# DaughterBoard.net
KiCad netlist of a schematic drawn in Altium Designer
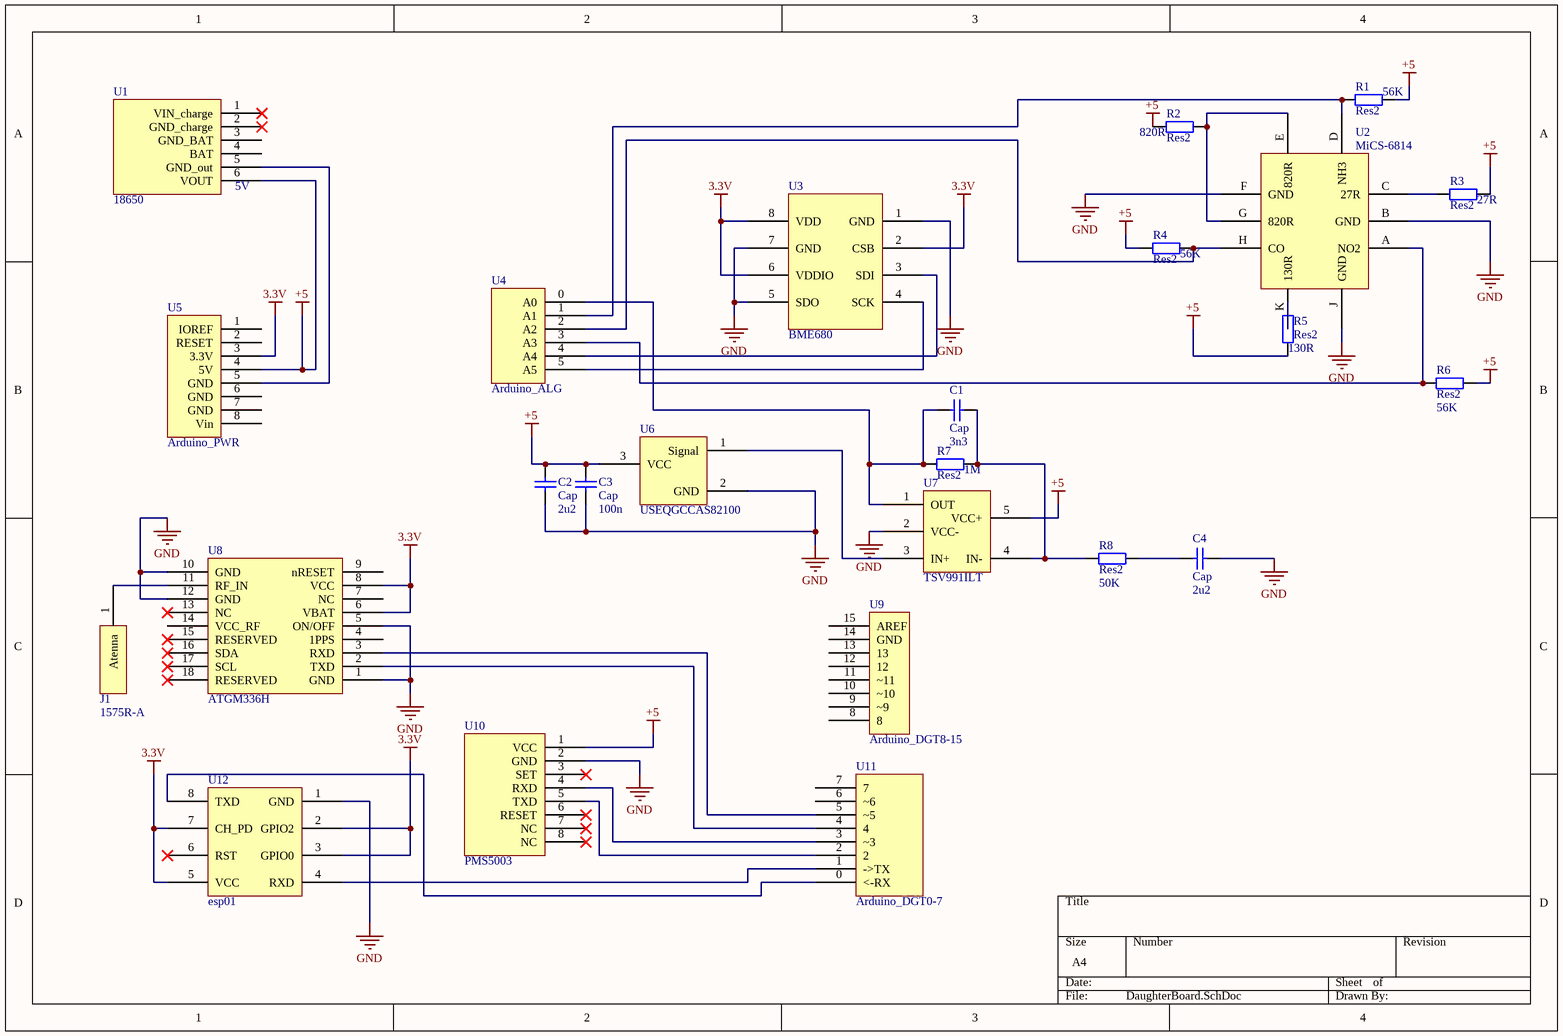
[diagram p0: DaughterBoard.SchDoc]

(export (version "E")
  (design (tool "Eeschema 10.0.6"))
  (components
    (comp (ref "C1")
      (value "Cap")
      (footprint "RAD-0.3")
      (description "Capacitor")
      (fields (field (name "ALTIUM_VALUE") "3n3") (field (name "PUBLISHER") "Altium Limited"))
      (libsource (lib "Miscellaneous Devices") (part "Cap"))
    )
    (comp (ref "C2")
      (value "Cap")
      (footprint "RAD-0.3")
      (description "Capacitor")
      (fields (field (name "ALTIUM_VALUE") "2u2") (field (name "PUBLISHER") "Altium Limited"))
      (libsource (lib "Miscellaneous Devices") (part "Cap"))
    )
    (comp (ref "C3")
      (value "Cap")
      (footprint "RAD-0.3")
      (description "Capacitor")
      (fields (field (name "ALTIUM_VALUE") "100n") (field (name "PUBLISHER") "Altium Limited"))
      (libsource (lib "Miscellaneous Devices") (part "Cap"))
    )
    (comp (ref "C4")
      (value "Cap")
      (footprint "RAD-0.3")
      (description "Capacitor")
      (fields (field (name "ALTIUM_VALUE") "2u2") (field (name "PUBLISHER") "Altium Limited"))
      (libsource (lib "Miscellaneous Devices") (part "Cap"))
    )
    (comp (ref "J1") (value "1575R-A") (libsource (lib "SDLib") (part "1575R-A")))
    (comp (ref "R1")
      (value "Res2")
      (footprint "AXIAL-0.4")
      (description "Resistor")
      (fields (field (name "ALTIUM_VALUE") "56K") (field (name "PUBLISHER") "Altium Limited"))
      (libsource (lib "") (part "Res2_2"))
    )
    (comp (ref "R2")
      (value "Res2")
      (footprint "AXIAL-0.4")
      (description "Resistor")
      (fields (field (name "ALTIUM_VALUE") "820R") (field (name "PUBLISHER") "Altium Limited"))
      (libsource (lib "Miscellaneous Devices") (part "Res2"))
    )
    (comp (ref "R3")
      (value "Res2")
      (footprint "AXIAL-0.4")
      (description "Resistor")
      (fields (field (name "ALTIUM_VALUE") "27R") (field (name "PUBLISHER") "Altium Limited"))
      (libsource (lib "Miscellaneous Devices") (part "Res2"))
    )
    (comp (ref "R4")
      (value "Res2")
      (footprint "AXIAL-0.4")
      (description "Resistor")
      (fields (field (name "ALTIUM_VALUE") "56K") (field (name "PUBLISHER") "Altium Limited"))
      (libsource (lib "Miscellaneous Devices") (part "Res2"))
    )
    (comp (ref "R5")
      (value "Res2")
      (footprint "AXIAL-0.4")
      (description "Resistor")
      (fields (field (name "ALTIUM_VALUE") "130R") (field (name "PUBLISHER") "Altium Limited"))
      (libsource (lib "") (part "Res2_1"))
    )
    (comp (ref "R6")
      (value "Res2")
      (footprint "AXIAL-0.4")
      (description "Resistor")
      (fields (field (name "ALTIUM_VALUE") "56K") (field (name "PUBLISHER") "Altium Limited"))
      (libsource (lib "") (part "Res2_2"))
    )
    (comp (ref "R7")
      (value "Res2")
      (footprint "AXIAL-0.4")
      (description "Resistor")
      (fields (field (name "ALTIUM_VALUE") "1M") (field (name "PUBLISHER") "Altium Limited"))
      (libsource (lib "Miscellaneous Devices") (part "Res2"))
    )
    (comp (ref "R8")
      (value "Res2")
      (footprint "AXIAL-0.4")
      (description "Resistor")
      (fields (field (name "ALTIUM_VALUE") "50K") (field (name "PUBLISHER") "Altium Limited"))
      (libsource (lib "") (part "Res2_2"))
    )
    (comp (ref "U1") (value "18650") (libsource (lib "SDLib") (part "18650")))
    (comp (ref "U2") (value "MiCS-6814") (libsource (lib "SDLib") (part "MiCS-6814")))
    (comp (ref "U3") (value "BME680") (libsource (lib "SDLib") (part "BME680")))
    (comp (ref "U4") (value "Arduino_ALG") (libsource (lib "SDLib") (part "Arduino_ALG")))
    (comp (ref "U5") (value "Arduino_PWR") (libsource (lib "SDLib") (part "Arduino_PWR")))
    (comp (ref "U6") (value "USEQGCCAS82100") (libsource (lib "SDLib") (part "USEQGCCAS82100")))
    (comp (ref "U7") (value "TSV991ILT") (libsource (lib "SDLib") (part "TSV991ILT")))
    (comp (ref "U8") (value "ATGM336H") (libsource (lib "SDLib") (part "ATGM336H")))
    (comp (ref "U9") (value "Arduino_DGT8-15") (libsource (lib "SDLib") (part "Arduino_DGT8-15")))
    (comp (ref "U10") (value "PMS5003") (libsource (lib "SDLib") (part "PMS5003")))
    (comp (ref "U11") (value "Arduino_DGT0-7") (libsource (lib "SDLib") (part "Arduino_DGT0-7")))
    (comp (ref "U12") (value "esp01") (libsource (lib "SDLib") (part "esp01")))
  )
  (nets
    (net (code "1") (name "+5") (class "Default")
      (node (ref "C2") (pin "2") (pinfunction "2_2") (pintype "passive"))
      (node (ref "C3") (pin "2") (pinfunction "2_2") (pintype "passive"))
      (node (ref "R1") (pin "1") (pinfunction "1_1") (pintype "passive"))
      (node (ref "R2") (pin "1") (pinfunction "1_1") (pintype "passive"))
      (node (ref "R3") (pin "2") (pinfunction "2_2") (pintype "passive"))
      (node (ref "R4") (pin "1") (pinfunction "1_1") (pintype "passive"))
      (node (ref "R5") (pin "1") (pinfunction "1_1") (pintype "passive"))
      (node (ref "R6") (pin "1") (pinfunction "1_1") (pintype "passive"))
      (node (ref "U1") (pin "6") (pinfunction "VOUT_6") (pintype "passive"))
      (node (ref "U10") (pin "1") (pinfunction "VCC_1") (pintype "passive"))
      (node (ref "U5") (pin "4") (pinfunction "5V_4") (pintype "passive"))
      (node (ref "U6") (pin "3") (pinfunction "VCC_3") (pintype "passive"))
      (node (ref "U7") (pin "5") (pinfunction "VCC+_5") (pintype "passive"))
    )
    (net (code "2") (name "3.3V") (class "Default")
      (node (ref "U12") (pin "2") (pinfunction "GPIO2_2") (pintype "passive"))
      (node (ref "U12") (pin "3") (pinfunction "GPIO0_3") (pintype "passive"))
      (node (ref "U12") (pin "5") (pinfunction "VCC_5") (pintype "passive"))
      (node (ref "U12") (pin "7") (pinfunction "CH_PD_7") (pintype "passive"))
      (node (ref "U3") (pin "2") (pinfunction "CSB_2") (pintype "passive"))
      (node (ref "U3") (pin "6") (pinfunction "VDDIO_6") (pintype "passive"))
      (node (ref "U3") (pin "8") (pinfunction "VDD_8") (pintype "passive"))
      (node (ref "U5") (pin "3") (pinfunction "3.3V_3") (pintype "power_in"))
      (node (ref "U8") (pin "6") (pinfunction "VBAT_6") (pintype "passive"))
      (node (ref "U8") (pin "8") (pinfunction "VCC_8") (pintype "passive"))
    )
    (net (code "3") (name "GND") (class "Default")
      (node (ref "C2") (pin "1") (pinfunction "1_1") (pintype "passive"))
      (node (ref "C3") (pin "1") (pinfunction "1_1") (pintype "passive"))
      (node (ref "C4") (pin "2") (pinfunction "2_2") (pintype "passive"))
      (node (ref "U10") (pin "2") (pinfunction "GND_2") (pintype "passive"))
      (node (ref "U12") (pin "1") (pinfunction "GND_1") (pintype "passive"))
      (node (ref "U2") (pin "B") (pinfunction "GND_B") (pintype "passive"))
      (node (ref "U2") (pin "F") (pinfunction "GND_F") (pintype "passive"))
      (node (ref "U2") (pin "J") (pinfunction "GND_J") (pintype "passive"))
      (node (ref "U3") (pin "1") (pinfunction "GND_1") (pintype "passive"))
      (node (ref "U3") (pin "5") (pinfunction "SDO_5") (pintype "passive"))
      (node (ref "U3") (pin "7") (pinfunction "GND_7") (pintype "passive"))
      (node (ref "U6") (pin "2") (pinfunction "GND_2") (pintype "passive"))
      (node (ref "U7") (pin "2") (pinfunction "VCC-_2") (pintype "passive"))
      (node (ref "U8") (pin "1") (pinfunction "GND_1") (pintype "passive"))
      (node (ref "U8") (pin "10") (pinfunction "GND_10") (pintype "passive"))
      (node (ref "U8") (pin "12") (pinfunction "GND_12") (pintype "passive"))
      (node (ref "U8") (pin "5") (pinfunction "ON/OFF_5") (pintype "passive"))
    )
    (net (code "4") (name "Net-(C4-Pad1)") (class "Default")
      (node (ref "C4") (pin "1") (pinfunction "1_1") (pintype "passive"))
      (node (ref "R8") (pin "1") (pinfunction "1_1") (pintype "passive"))
    )
    (net (code "5") (name "Net-(J1-Atenna)") (class "Default")
      (node (ref "J1") (pin "1") (pinfunction "Atenna_1") (pintype "passive"))
      (node (ref "U8") (pin "11") (pinfunction "RF_IN_11") (pintype "passive"))
    )
    (net (code "6") (name "Net-(R2-Pad2)") (class "Default")
      (node (ref "R2") (pin "2") (pinfunction "2_2") (pintype "passive"))
      (node (ref "U2") (pin "E") (pinfunction "820R_E") (pintype "passive"))
      (node (ref "U2") (pin "G") (pinfunction "820R_G") (pintype "passive"))
    )
    (net (code "7") (name "Net-(U1-GND_out)") (class "Default")
      (node (ref "U1") (pin "5") (pinfunction "GND_out_5") (pintype "passive"))
      (node (ref "U5") (pin "5") (pinfunction "GND_5") (pintype "power_in"))
    )
    (net (code "8") (name "Net-(U2-27R)") (class "Default")
      (node (ref "R3") (pin "1") (pinfunction "1_1") (pintype "passive"))
      (node (ref "U2") (pin "C") (pinfunction "27R_C") (pintype "passive"))
    )
    (net (code "9") (name "Net-(U2-130R)") (class "Default")
      (node (ref "R5") (pin "2") (pinfunction "2_2") (pintype "passive"))
      (node (ref "U2") (pin "K") (pinfunction "130R_K") (pintype "passive"))
    )
    (net (code "10") (name "Net-(U2-CO)") (class "Default")
      (node (ref "R4") (pin "2") (pinfunction "2_2") (pintype "passive"))
      (node (ref "U2") (pin "H") (pinfunction "CO_H") (pintype "passive"))
      (node (ref "U4") (pin "2") (pinfunction "A2_2") (pintype "passive"))
    )
    (net (code "11") (name "Net-(U2-NH3)") (class "Default")
      (node (ref "R1") (pin "2") (pinfunction "2_2") (pintype "passive"))
      (node (ref "U2") (pin "D") (pinfunction "NH3_D") (pintype "passive"))
      (node (ref "U4") (pin "1") (pinfunction "A1_1") (pintype "passive"))
    )
    (net (code "12") (name "Net-(U2-NO2)") (class "Default")
      (node (ref "R6") (pin "2") (pinfunction "2_2") (pintype "passive"))
      (node (ref "U2") (pin "A") (pinfunction "NO2_A") (pintype "passive"))
      (node (ref "U4") (pin "3") (pinfunction "A3_3") (pintype "passive"))
    )
    (net (code "13") (name "Net-(U3-SCK)") (class "Default")
      (node (ref "U3") (pin "4") (pinfunction "SCK_4") (pintype "passive"))
      (node (ref "U4") (pin "5") (pinfunction "A5_5") (pintype "passive"))
    )
    (net (code "14") (name "Net-(U3-SDI)") (class "Default")
      (node (ref "U3") (pin "3") (pinfunction "SDI_3") (pintype "passive"))
      (node (ref "U4") (pin "4") (pinfunction "A4_4") (pintype "passive"))
    )
    (net (code "15") (name "Net-(U4-A0)") (class "Default")
      (node (ref "C1") (pin "2") (pinfunction "2_2") (pintype "passive"))
      (node (ref "R7") (pin "1") (pinfunction "1_1") (pintype "passive"))
      (node (ref "U4") (pin "0") (pinfunction "A0_0") (pintype "passive"))
      (node (ref "U7") (pin "1") (pinfunction "OUT_1") (pintype "passive"))
    )
    (net (code "16") (name "Net-(U6-Signal)") (class "Default")
      (node (ref "U6") (pin "1") (pinfunction "Signal_1") (pintype "passive"))
      (node (ref "U7") (pin "3") (pinfunction "IN+_3") (pintype "passive"))
    )
    (net (code "17") (name "Net-(U7-IN-)") (class "Default")
      (node (ref "C1") (pin "1") (pinfunction "1_1") (pintype "passive"))
      (node (ref "R7") (pin "2") (pinfunction "2_2") (pintype "passive"))
      (node (ref "R8") (pin "2") (pinfunction "2_2") (pintype "passive"))
      (node (ref "U7") (pin "4") (pinfunction "IN-_4") (pintype "passive"))
    )
    (net (code "18") (name "Net-(U8-TXD)") (class "Default")
      (node (ref "U11") (pin "4") (pinfunction "4_4") (pintype "passive"))
      (node (ref "U8") (pin "2") (pinfunction "TXD_2") (pintype "passive"))
    )
    (net (code "19") (name "Net-(U10-RXD)") (class "Default")
      (node (ref "U10") (pin "4") (pinfunction "RXD_4") (pintype "passive"))
      (node (ref "U11") (pin "3") (pinfunction "~3_3") (pintype "passive"))
    )
    (net (code "20") (name "Net-(U10-TXD)") (class "Default")
      (node (ref "U10") (pin "5") (pinfunction "TXD_5") (pintype "passive"))
      (node (ref "U11") (pin "2") (pinfunction "2_2") (pintype "passive"))
    )
    (net (code "21") (name "Net-(U11-->TX)") (class "Default")
      (node (ref "U11") (pin "1") (pinfunction "->TX_1") (pintype "passive"))
      (node (ref "U12") (pin "4") (pinfunction "RXD_4") (pintype "passive"))
    )
    (net (code "22") (name "Net-(U11-<-RX)") (class "Default")
      (node (ref "U11") (pin "0") (pinfunction "<-RX_0") (pintype "passive"))
      (node (ref "U12") (pin "8") (pinfunction "TXD_8") (pintype "passive"))
    )
    (net (code "23") (name "Net-(U11-~5)") (class "Default")
      (node (ref "U11") (pin "5") (pinfunction "~5_5") (pintype "passive"))
      (node (ref "U8") (pin "3") (pinfunction "RXD_3") (pintype "passive"))
    )
    (net (code "24") (name "unconnected-(U1-BAT-Pad4)") (class "Default")
      (node (ref "U1") (pin "4") (pinfunction "BAT_4") (pintype "passive"))
    )
    (net (code "25") (name "unconnected-(U1-GND_BAT-Pad3)") (class "Default")
      (node (ref "U1") (pin "3") (pinfunction "GND_BAT_3") (pintype "passive"))
    )
    (net (code "26") (name "unconnected-(U1-GND_charge-Pad2)") (class "Default")
      (node (ref "U1") (pin "2") (pinfunction "GND_charge_2") (pintype "passive+no_connect"))
    )
    (net (code "27") (name "unconnected-(U1-VIN_charge-Pad1)") (class "Default")
      (node (ref "U1") (pin "1") (pinfunction "VIN_charge_1") (pintype "passive+no_connect"))
    )
    (net (code "28") (name "unconnected-(U5-GND-Pad6)") (class "Default")
      (node (ref "U5") (pin "6") (pinfunction "GND_6") (pintype "power_in"))
    )
    (net (code "29") (name "unconnected-(U5-GND-Pad7)") (class "Default")
      (node (ref "U5") (pin "7") (pinfunction "GND_7") (pintype "power_in"))
    )
    (net (code "30") (name "unconnected-(U5-IOREF-Pad1)") (class "Default")
      (node (ref "U5") (pin "1") (pinfunction "IOREF_1") (pintype "passive"))
    )
    (net (code "31") (name "unconnected-(U5-RESET-Pad2)") (class "Default")
      (node (ref "U5") (pin "2") (pinfunction "RESET_2") (pintype "power_in"))
    )
    (net (code "32") (name "unconnected-(U5-Vin-Pad8)") (class "Default")
      (node (ref "U5") (pin "8") (pinfunction "Vin_8") (pintype "power_in"))
    )
    (net (code "33") (name "unconnected-(U8-1PPS-Pad4)") (class "Default")
      (node (ref "U8") (pin "4") (pinfunction "1PPS_4") (pintype "passive"))
    )
    (net (code "34") (name "unconnected-(U8-NC-Pad7)") (class "Default")
      (node (ref "U8") (pin "7") (pinfunction "NC_7") (pintype "passive"))
    )
    (net (code "35") (name "unconnected-(U8-NC-Pad13)") (class "Default")
      (node (ref "U8") (pin "13") (pinfunction "NC_13") (pintype "passive+no_connect"))
    )
    (net (code "36") (name "unconnected-(U8-RESERVED-Pad15)") (class "Default")
      (node (ref "U8") (pin "15") (pinfunction "RESERVED_15") (pintype "passive+no_connect"))
    )
    (net (code "37") (name "unconnected-(U8-RESERVED-Pad18)") (class "Default")
      (node (ref "U8") (pin "18") (pinfunction "RESERVED_18") (pintype "passive+no_connect"))
    )
    (net (code "38") (name "unconnected-(U8-SCL-Pad17)") (class "Default")
      (node (ref "U8") (pin "17") (pinfunction "SCL_17") (pintype "passive+no_connect"))
    )
    (net (code "39") (name "unconnected-(U8-SDA-Pad16)") (class "Default")
      (node (ref "U8") (pin "16") (pinfunction "SDA_16") (pintype "passive+no_connect"))
    )
    (net (code "40") (name "unconnected-(U8-VCC_RF-Pad14)") (class "Default")
      (node (ref "U8") (pin "14") (pinfunction "VCC_RF_14") (pintype "passive"))
    )
    (net (code "41") (name "unconnected-(U8-nRESET-Pad9)") (class "Default")
      (node (ref "U8") (pin "9") (pinfunction "nRESET_9") (pintype "passive"))
    )
    (net (code "42") (name "unconnected-(U9-AREF-Pad15)") (class "Default")
      (node (ref "U9") (pin "15") (pinfunction "AREF_15") (pintype "passive"))
    )
    (net (code "43") (name "unconnected-(U9-GND-Pad14)") (class "Default")
      (node (ref "U9") (pin "14") (pinfunction "GND_14") (pintype "passive"))
    )
    (net (code "44") (name "unconnected-(U9-Pad8)") (class "Default")
      (node (ref "U9") (pin "8") (pinfunction "8_8") (pintype "passive"))
    )
    (net (code "45") (name "unconnected-(U9-Pad12)") (class "Default")
      (node (ref "U9") (pin "12") (pinfunction "12_12") (pintype "passive"))
    )
    (net (code "46") (name "unconnected-(U9-Pad13)") (class "Default")
      (node (ref "U9") (pin "13") (pinfunction "13_13") (pintype "passive"))
    )
    (net (code "47") (name "unconnected-(U9-~9-Pad9)") (class "Default")
      (node (ref "U9") (pin "9") (pinfunction "~9_9") (pintype "passive"))
    )
    (net (code "48") (name "unconnected-(U9-~10-Pad10)") (class "Default")
      (node (ref "U9") (pin "10") (pinfunction "~10_10") (pintype "passive"))
    )
    (net (code "49") (name "unconnected-(U9-~11-Pad11)") (class "Default")
      (node (ref "U9") (pin "11") (pinfunction "~11_11") (pintype "passive"))
    )
    (net (code "50") (name "unconnected-(U10-NC-Pad7)") (class "Default")
      (node (ref "U10") (pin "7") (pinfunction "NC_7") (pintype "passive+no_connect"))
    )
    (net (code "51") (name "unconnected-(U10-NC-Pad8)") (class "Default")
      (node (ref "U10") (pin "8") (pinfunction "NC_8") (pintype "passive+no_connect"))
    )
    (net (code "52") (name "unconnected-(U10-RESET-Pad6)") (class "Default")
      (node (ref "U10") (pin "6") (pinfunction "RESET_6") (pintype "passive+no_connect"))
    )
    (net (code "53") (name "unconnected-(U10-SET-Pad3)") (class "Default")
      (node (ref "U10") (pin "3") (pinfunction "SET_3") (pintype "passive+no_connect"))
    )
    (net (code "54") (name "unconnected-(U11-Pad7)") (class "Default")
      (node (ref "U11") (pin "7") (pinfunction "7_7") (pintype "passive"))
    )
    (net (code "55") (name "unconnected-(U11-~6-Pad6)") (class "Default")
      (node (ref "U11") (pin "6") (pinfunction "~6_6") (pintype "passive"))
    )
    (net (code "56") (name "unconnected-(U12-RST-Pad6)") (class "Default")
      (node (ref "U12") (pin "6") (pinfunction "RST_6") (pintype "passive+no_connect"))
    )
  )
)
